# BMS_Enerdel_Adapter_rev5.net
KiCad netlist of a schematic drawn in EAGLE
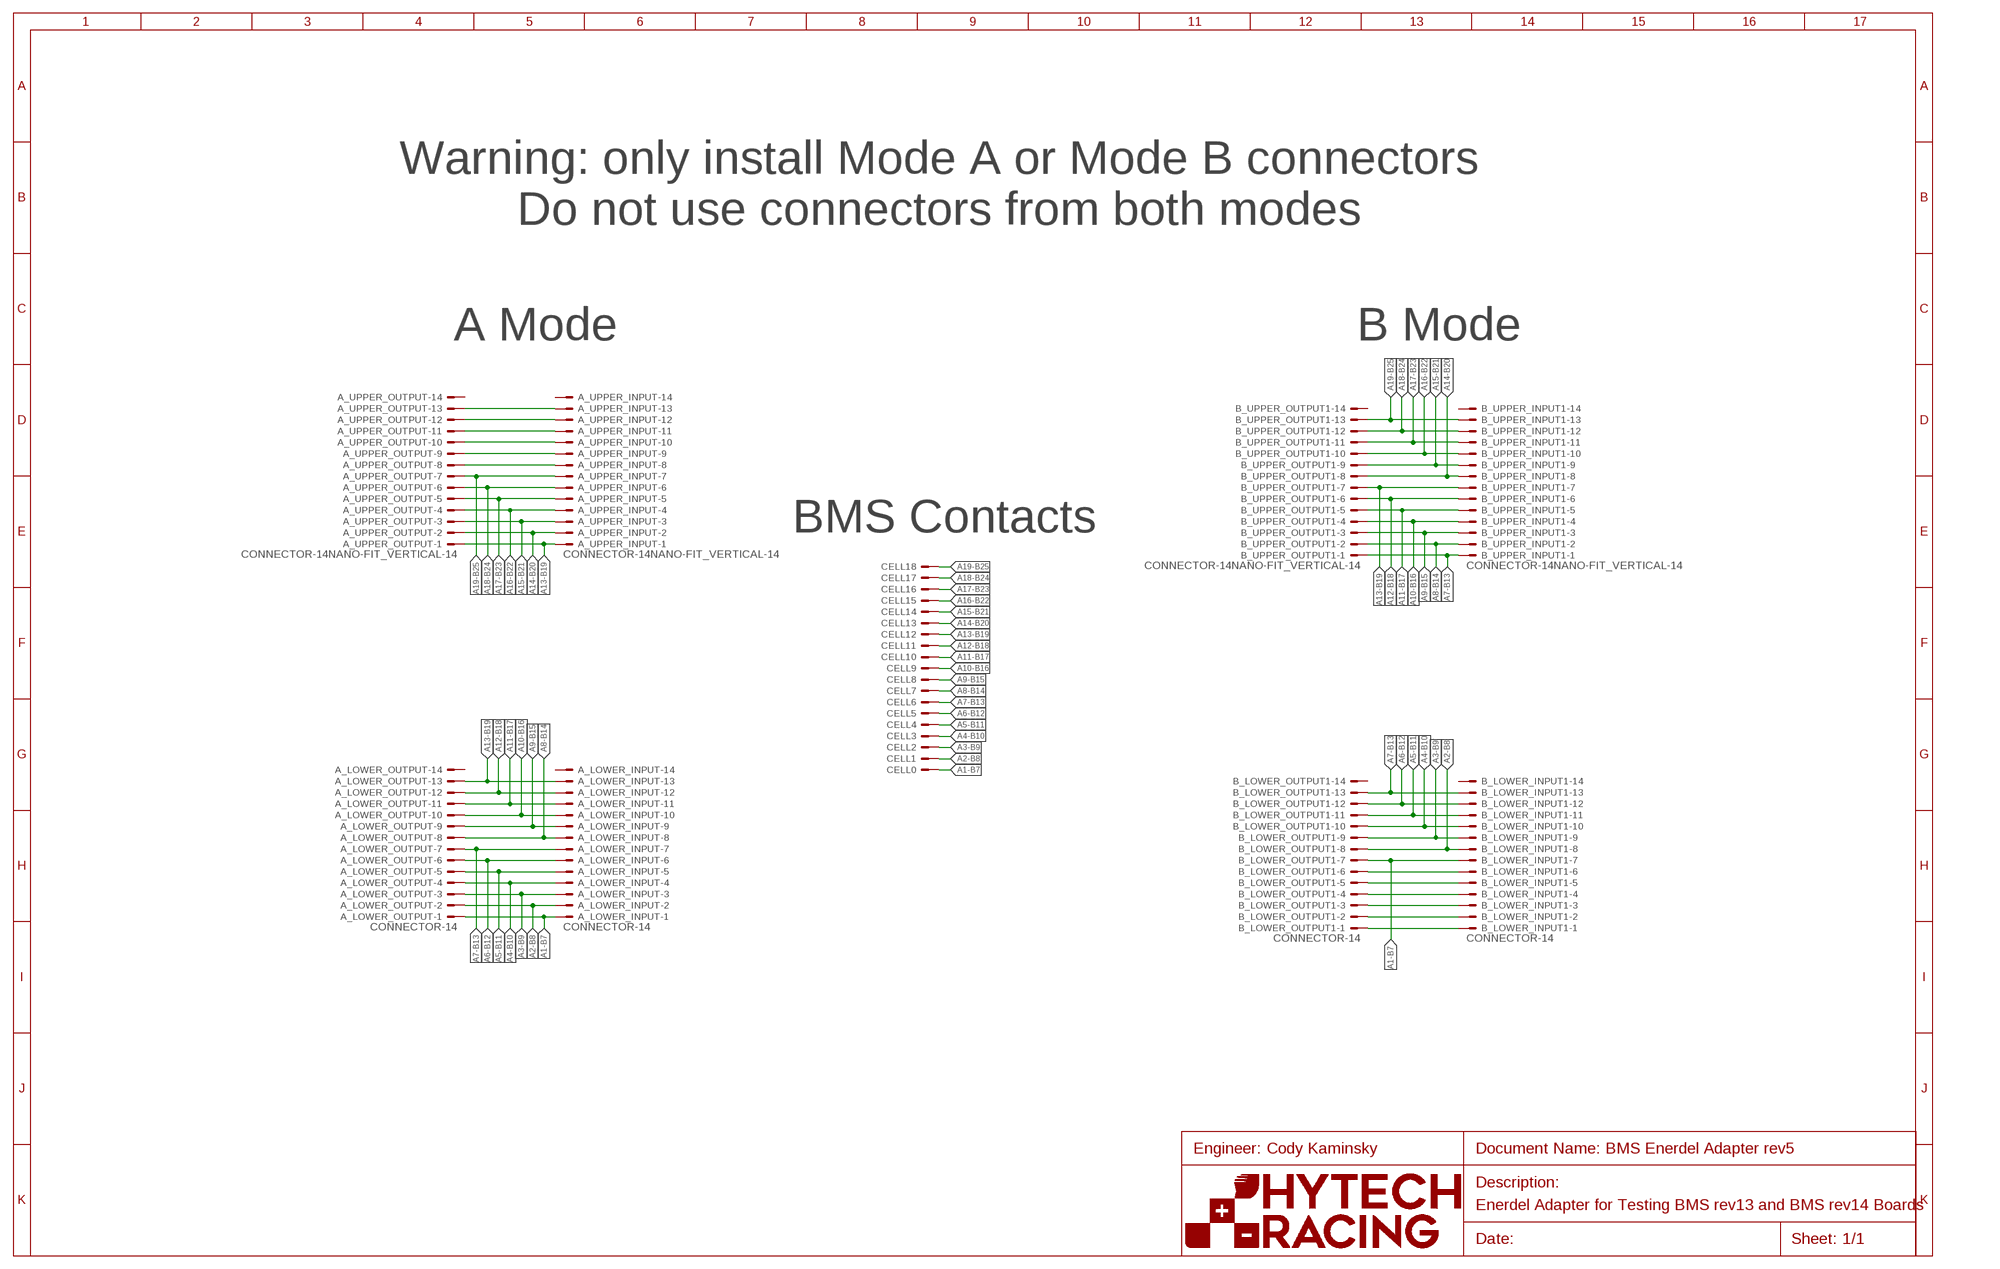
[diagram p0: schematic, sheet 1]

(export (version "E")
  (design (tool "Eeschema 10.0.6"))
  (components
    (comp (ref "A_LOWER_INPUT")
      (value "CONNECTOR-14")
      (footprint "eagle-import:MINIFIT_5566-14")
      (libsource (lib "eagle-import") (part "CONNECTOR-14"))
    )
    (comp (ref "A_LOWER_OUTPUT")
      (value "CONNECTOR-14")
      (footprint "eagle-import:MINIFIT_5566-14")
      (libsource (lib "eagle-import") (part "CONNECTOR-14"))
    )
    (comp (ref "A_UPPER_INPUT")
      (value "CONNECTOR-14NANO-FIT_VERTICAL-14")
      (footprint "eagle-import:NANO-FIT_VERTICAL-14")
      (libsource (lib "eagle-import") (part "CONNECTOR-14NANO-FIT_VERTICAL-14"))
    )
    (comp (ref "A_UPPER_OUTPUT")
      (value "CONNECTOR-14NANO-FIT_VERTICAL-14")
      (footprint "eagle-import:NANO-FIT_VERTICAL-14")
      (libsource (lib "eagle-import") (part "CONNECTOR-14NANO-FIT_VERTICAL-14"))
    )
    (comp (ref "B_LOWER_INPUT1")
      (value "CONNECTOR-14")
      (footprint "eagle-import:MINIFIT_5566-14")
      (libsource (lib "eagle-import") (part "CONNECTOR-14"))
    )
    (comp (ref "B_LOWER_OUTPUT1")
      (value "CONNECTOR-14")
      (footprint "eagle-import:MINIFIT_5566-14")
      (libsource (lib "eagle-import") (part "CONNECTOR-14"))
    )
    (comp (ref "B_UPPER_INPUT1")
      (value "CONNECTOR-14NANO-FIT_VERTICAL-14")
      (footprint "eagle-import:NANO-FIT_VERTICAL-14")
      (libsource (lib "eagle-import") (part "CONNECTOR-14NANO-FIT_VERTICAL-14"))
    )
    (comp (ref "B_UPPER_OUTPUT1")
      (value "CONNECTOR-14NANO-FIT_VERTICAL-14")
      (footprint "eagle-import:NANO-FIT_VERTICAL-14")
      (libsource (lib "eagle-import") (part "CONNECTOR-14NANO-FIT_VERTICAL-14"))
    )
    (comp (ref "CELL0")
      (value "BATTERY_SPRING_KEYSTONE5222")
      (footprint "eagle-import:KEYSTONE5222")
      (libsource (lib "eagle-import") (part "BATTERY_SPRING_KEYSTONE5222"))
    )
    (comp (ref "CELL1")
      (value "BATTERY_SPRING_KEYSTONE5222")
      (footprint "eagle-import:KEYSTONE5222")
      (libsource (lib "eagle-import") (part "BATTERY_SPRING_KEYSTONE5222"))
    )
    (comp (ref "CELL2")
      (value "BATTERY_SPRING_KEYSTONE5222")
      (footprint "eagle-import:KEYSTONE5222")
      (libsource (lib "eagle-import") (part "BATTERY_SPRING_KEYSTONE5222"))
    )
    (comp (ref "CELL3")
      (value "BATTERY_SPRING_KEYSTONE5222")
      (footprint "eagle-import:KEYSTONE5222")
      (libsource (lib "eagle-import") (part "BATTERY_SPRING_KEYSTONE5222"))
    )
    (comp (ref "CELL4")
      (value "BATTERY_SPRING_KEYSTONE5222")
      (footprint "eagle-import:KEYSTONE5222")
      (libsource (lib "eagle-import") (part "BATTERY_SPRING_KEYSTONE5222"))
    )
    (comp (ref "CELL5")
      (value "BATTERY_SPRING_KEYSTONE5222")
      (footprint "eagle-import:KEYSTONE5222")
      (libsource (lib "eagle-import") (part "BATTERY_SPRING_KEYSTONE5222"))
    )
    (comp (ref "CELL6")
      (value "BATTERY_SPRING_KEYSTONE5222")
      (footprint "eagle-import:KEYSTONE5222")
      (libsource (lib "eagle-import") (part "BATTERY_SPRING_KEYSTONE5222"))
    )
    (comp (ref "CELL7")
      (value "BATTERY_SPRING_KEYSTONE5222")
      (footprint "eagle-import:KEYSTONE5222")
      (libsource (lib "eagle-import") (part "BATTERY_SPRING_KEYSTONE5222"))
    )
    (comp (ref "CELL8")
      (value "BATTERY_SPRING_KEYSTONE5222")
      (footprint "eagle-import:KEYSTONE5222")
      (libsource (lib "eagle-import") (part "BATTERY_SPRING_KEYSTONE5222"))
    )
    (comp (ref "CELL9")
      (value "BATTERY_SPRING_KEYSTONE5222")
      (footprint "eagle-import:KEYSTONE5222")
      (libsource (lib "eagle-import") (part "BATTERY_SPRING_KEYSTONE5222"))
    )
    (comp (ref "CELL10")
      (value "BATTERY_SPRING_KEYSTONE5222")
      (footprint "eagle-import:KEYSTONE5222")
      (libsource (lib "eagle-import") (part "BATTERY_SPRING_KEYSTONE5222"))
    )
    (comp (ref "CELL11")
      (value "BATTERY_SPRING_KEYSTONE5222")
      (footprint "eagle-import:KEYSTONE5222")
      (libsource (lib "eagle-import") (part "BATTERY_SPRING_KEYSTONE5222"))
    )
    (comp (ref "CELL12")
      (value "BATTERY_SPRING_KEYSTONE5222")
      (footprint "eagle-import:KEYSTONE5222")
      (libsource (lib "eagle-import") (part "BATTERY_SPRING_KEYSTONE5222"))
    )
    (comp (ref "CELL13")
      (value "BATTERY_SPRING_KEYSTONE5222")
      (footprint "eagle-import:KEYSTONE5222")
      (libsource (lib "eagle-import") (part "BATTERY_SPRING_KEYSTONE5222"))
    )
    (comp (ref "CELL14")
      (value "BATTERY_SPRING_KEYSTONE5222")
      (footprint "eagle-import:KEYSTONE5222")
      (libsource (lib "eagle-import") (part "BATTERY_SPRING_KEYSTONE5222"))
    )
    (comp (ref "CELL15")
      (value "BATTERY_SPRING_KEYSTONE5222")
      (footprint "eagle-import:KEYSTONE5222")
      (libsource (lib "eagle-import") (part "BATTERY_SPRING_KEYSTONE5222"))
    )
    (comp (ref "CELL16")
      (value "BATTERY_SPRING_KEYSTONE5222")
      (footprint "eagle-import:KEYSTONE5222")
      (libsource (lib "eagle-import") (part "BATTERY_SPRING_KEYSTONE5222"))
    )
    (comp (ref "CELL17")
      (value "BATTERY_SPRING_KEYSTONE5222")
      (footprint "eagle-import:KEYSTONE5222")
      (libsource (lib "eagle-import") (part "BATTERY_SPRING_KEYSTONE5222"))
    )
    (comp (ref "CELL18")
      (value "BATTERY_SPRING_KEYSTONE5222")
      (footprint "eagle-import:KEYSTONE5222")
      (libsource (lib "eagle-import") (part "BATTERY_SPRING_KEYSTONE5222"))
    )
  )
  (nets
    (net (code "1") (name "A1-B7") (class "Default")
      (node (ref "A_LOWER_INPUT") (pin "1") (pinfunction "S_1") (pintype "passive"))
      (node (ref "A_LOWER_OUTPUT") (pin "1") (pinfunction "S_1") (pintype "passive"))
      (node (ref "B_LOWER_INPUT1") (pin "7") (pinfunction "S_7") (pintype "passive"))
      (node (ref "B_LOWER_OUTPUT1") (pin "7") (pinfunction "S_7") (pintype "passive"))
      (node (ref "CELL0") (pin "P$1") (pinfunction "S_P$1") (pintype "passive"))
    )
    (net (code "2") (name "A2-B8") (class "Default")
      (node (ref "A_LOWER_INPUT") (pin "2") (pinfunction "S_2") (pintype "passive"))
      (node (ref "A_LOWER_OUTPUT") (pin "2") (pinfunction "S_2") (pintype "passive"))
      (node (ref "B_LOWER_INPUT1") (pin "8") (pinfunction "S_8") (pintype "passive"))
      (node (ref "B_LOWER_OUTPUT1") (pin "8") (pinfunction "S_8") (pintype "passive"))
      (node (ref "CELL1") (pin "P$1") (pinfunction "S_P$1") (pintype "passive"))
    )
    (net (code "3") (name "A3-B9") (class "Default")
      (node (ref "A_LOWER_INPUT") (pin "3") (pinfunction "S_3") (pintype "passive"))
      (node (ref "A_LOWER_OUTPUT") (pin "3") (pinfunction "S_3") (pintype "passive"))
      (node (ref "B_LOWER_INPUT1") (pin "9") (pinfunction "S_9") (pintype "passive"))
      (node (ref "B_LOWER_OUTPUT1") (pin "9") (pinfunction "S_9") (pintype "passive"))
      (node (ref "CELL2") (pin "P$1") (pinfunction "S_P$1") (pintype "passive"))
    )
    (net (code "4") (name "A4-B10") (class "Default")
      (node (ref "A_LOWER_INPUT") (pin "4") (pinfunction "S_4") (pintype "passive"))
      (node (ref "A_LOWER_OUTPUT") (pin "4") (pinfunction "S_4") (pintype "passive"))
      (node (ref "B_LOWER_INPUT1") (pin "10") (pinfunction "S_10") (pintype "passive"))
      (node (ref "B_LOWER_OUTPUT1") (pin "10") (pinfunction "S_10") (pintype "passive"))
      (node (ref "CELL3") (pin "P$1") (pinfunction "S_P$1") (pintype "passive"))
    )
    (net (code "5") (name "A5-B11") (class "Default")
      (node (ref "A_LOWER_INPUT") (pin "5") (pinfunction "S_5") (pintype "passive"))
      (node (ref "A_LOWER_OUTPUT") (pin "5") (pinfunction "S_5") (pintype "passive"))
      (node (ref "B_LOWER_INPUT1") (pin "11") (pinfunction "S_11") (pintype "passive"))
      (node (ref "B_LOWER_OUTPUT1") (pin "11") (pinfunction "S_11") (pintype "passive"))
      (node (ref "CELL4") (pin "P$1") (pinfunction "S_P$1") (pintype "passive"))
    )
    (net (code "6") (name "A6-B12") (class "Default")
      (node (ref "A_LOWER_INPUT") (pin "6") (pinfunction "S_6") (pintype "passive"))
      (node (ref "A_LOWER_OUTPUT") (pin "6") (pinfunction "S_6") (pintype "passive"))
      (node (ref "B_LOWER_INPUT1") (pin "12") (pinfunction "S_12") (pintype "passive"))
      (node (ref "B_LOWER_OUTPUT1") (pin "12") (pinfunction "S_12") (pintype "passive"))
      (node (ref "CELL5") (pin "P$1") (pinfunction "S_P$1") (pintype "passive"))
    )
    (net (code "7") (name "A7-B13") (class "Default")
      (node (ref "A_LOWER_INPUT") (pin "7") (pinfunction "S_7") (pintype "passive"))
      (node (ref "A_LOWER_OUTPUT") (pin "7") (pinfunction "S_7") (pintype "passive"))
      (node (ref "B_LOWER_INPUT1") (pin "13") (pinfunction "S_13") (pintype "passive"))
      (node (ref "B_LOWER_OUTPUT1") (pin "13") (pinfunction "S_13") (pintype "passive"))
      (node (ref "B_UPPER_INPUT1") (pin "P$1") (pinfunction "S_P$1") (pintype "passive"))
      (node (ref "B_UPPER_OUTPUT1") (pin "P$1") (pinfunction "S_P$1") (pintype "passive"))
      (node (ref "CELL6") (pin "P$1") (pinfunction "S_P$1") (pintype "passive"))
    )
    (net (code "8") (name "A8-B14") (class "Default")
      (node (ref "A_LOWER_INPUT") (pin "8") (pinfunction "S_8") (pintype "passive"))
      (node (ref "A_LOWER_OUTPUT") (pin "8") (pinfunction "S_8") (pintype "passive"))
      (node (ref "B_UPPER_INPUT1") (pin "P$2") (pinfunction "S_P$2") (pintype "passive"))
      (node (ref "B_UPPER_OUTPUT1") (pin "P$2") (pinfunction "S_P$2") (pintype "passive"))
      (node (ref "CELL7") (pin "P$1") (pinfunction "S_P$1") (pintype "passive"))
    )
    (net (code "9") (name "A9-B15") (class "Default")
      (node (ref "A_LOWER_INPUT") (pin "9") (pinfunction "S_9") (pintype "passive"))
      (node (ref "A_LOWER_OUTPUT") (pin "9") (pinfunction "S_9") (pintype "passive"))
      (node (ref "B_UPPER_INPUT1") (pin "P$3") (pinfunction "S_P$3") (pintype "passive"))
      (node (ref "B_UPPER_OUTPUT1") (pin "P$3") (pinfunction "S_P$3") (pintype "passive"))
      (node (ref "CELL8") (pin "P$1") (pinfunction "S_P$1") (pintype "passive"))
    )
    (net (code "10") (name "A10-B16") (class "Default")
      (node (ref "A_LOWER_INPUT") (pin "10") (pinfunction "S_10") (pintype "passive"))
      (node (ref "A_LOWER_OUTPUT") (pin "10") (pinfunction "S_10") (pintype "passive"))
      (node (ref "B_UPPER_INPUT1") (pin "P$4") (pinfunction "S_P$4") (pintype "passive"))
      (node (ref "B_UPPER_OUTPUT1") (pin "P$4") (pinfunction "S_P$4") (pintype "passive"))
      (node (ref "CELL9") (pin "P$1") (pinfunction "S_P$1") (pintype "passive"))
    )
    (net (code "11") (name "A11-B17") (class "Default")
      (node (ref "A_LOWER_INPUT") (pin "11") (pinfunction "S_11") (pintype "passive"))
      (node (ref "A_LOWER_OUTPUT") (pin "11") (pinfunction "S_11") (pintype "passive"))
      (node (ref "B_UPPER_INPUT1") (pin "P$5") (pinfunction "S_P$5") (pintype "passive"))
      (node (ref "B_UPPER_OUTPUT1") (pin "P$5") (pinfunction "S_P$5") (pintype "passive"))
      (node (ref "CELL10") (pin "P$1") (pinfunction "S_P$1") (pintype "passive"))
    )
    (net (code "12") (name "A12-B18") (class "Default")
      (node (ref "A_LOWER_INPUT") (pin "12") (pinfunction "S_12") (pintype "passive"))
      (node (ref "A_LOWER_OUTPUT") (pin "12") (pinfunction "S_12") (pintype "passive"))
      (node (ref "B_UPPER_INPUT1") (pin "P$6") (pinfunction "S_P$6") (pintype "passive"))
      (node (ref "B_UPPER_OUTPUT1") (pin "P$6") (pinfunction "S_P$6") (pintype "passive"))
      (node (ref "CELL11") (pin "P$1") (pinfunction "S_P$1") (pintype "passive"))
    )
    (net (code "13") (name "A13-B19") (class "Default")
      (node (ref "A_LOWER_INPUT") (pin "13") (pinfunction "S_13") (pintype "passive"))
      (node (ref "A_LOWER_OUTPUT") (pin "13") (pinfunction "S_13") (pintype "passive"))
      (node (ref "A_UPPER_INPUT") (pin "P$1") (pinfunction "S_P$1") (pintype "passive"))
      (node (ref "A_UPPER_OUTPUT") (pin "P$1") (pinfunction "S_P$1") (pintype "passive"))
      (node (ref "B_UPPER_INPUT1") (pin "P$7") (pinfunction "S_P$7") (pintype "passive"))
      (node (ref "B_UPPER_OUTPUT1") (pin "P$7") (pinfunction "S_P$7") (pintype "passive"))
      (node (ref "CELL12") (pin "P$1") (pinfunction "S_P$1") (pintype "passive"))
    )
    (net (code "14") (name "A14-B20") (class "Default")
      (node (ref "A_UPPER_INPUT") (pin "P$2") (pinfunction "S_P$2") (pintype "passive"))
      (node (ref "A_UPPER_OUTPUT") (pin "P$2") (pinfunction "S_P$2") (pintype "passive"))
      (node (ref "B_UPPER_INPUT1") (pin "P$8") (pinfunction "S_P$8") (pintype "passive"))
      (node (ref "B_UPPER_OUTPUT1") (pin "P$8") (pinfunction "S_P$8") (pintype "passive"))
      (node (ref "CELL13") (pin "P$1") (pinfunction "S_P$1") (pintype "passive"))
    )
    (net (code "15") (name "A15-B21") (class "Default")
      (node (ref "A_UPPER_INPUT") (pin "P$3") (pinfunction "S_P$3") (pintype "passive"))
      (node (ref "A_UPPER_OUTPUT") (pin "P$3") (pinfunction "S_P$3") (pintype "passive"))
      (node (ref "B_UPPER_INPUT1") (pin "P$9") (pinfunction "S_P$9") (pintype "passive"))
      (node (ref "B_UPPER_OUTPUT1") (pin "P$9") (pinfunction "S_P$9") (pintype "passive"))
      (node (ref "CELL14") (pin "P$1") (pinfunction "S_P$1") (pintype "passive"))
    )
    (net (code "16") (name "A16-B22") (class "Default")
      (node (ref "A_UPPER_INPUT") (pin "P$4") (pinfunction "S_P$4") (pintype "passive"))
      (node (ref "A_UPPER_OUTPUT") (pin "P$4") (pinfunction "S_P$4") (pintype "passive"))
      (node (ref "B_UPPER_INPUT1") (pin "P$10") (pinfunction "S_P$10") (pintype "passive"))
      (node (ref "B_UPPER_OUTPUT1") (pin "P$10") (pinfunction "S_P$10") (pintype "passive"))
      (node (ref "CELL15") (pin "P$1") (pinfunction "S_P$1") (pintype "passive"))
    )
    (net (code "17") (name "A17-B23") (class "Default")
      (node (ref "A_UPPER_INPUT") (pin "P$5") (pinfunction "S_P$5") (pintype "passive"))
      (node (ref "A_UPPER_OUTPUT") (pin "P$5") (pinfunction "S_P$5") (pintype "passive"))
      (node (ref "B_UPPER_INPUT1") (pin "P$11") (pinfunction "S_P$11") (pintype "passive"))
      (node (ref "B_UPPER_OUTPUT1") (pin "P$11") (pinfunction "S_P$11") (pintype "passive"))
      (node (ref "CELL16") (pin "P$1") (pinfunction "S_P$1") (pintype "passive"))
    )
    (net (code "18") (name "A18-B24") (class "Default")
      (node (ref "A_UPPER_INPUT") (pin "P$6") (pinfunction "S_P$6") (pintype "passive"))
      (node (ref "A_UPPER_OUTPUT") (pin "P$6") (pinfunction "S_P$6") (pintype "passive"))
      (node (ref "B_UPPER_INPUT1") (pin "P$12") (pinfunction "S_P$12") (pintype "passive"))
      (node (ref "B_UPPER_OUTPUT1") (pin "P$12") (pinfunction "S_P$12") (pintype "passive"))
      (node (ref "CELL17") (pin "P$1") (pinfunction "S_P$1") (pintype "passive"))
    )
    (net (code "19") (name "A19-B25") (class "Default")
      (node (ref "A_UPPER_INPUT") (pin "P$7") (pinfunction "S_P$7") (pintype "passive"))
      (node (ref "A_UPPER_OUTPUT") (pin "P$7") (pinfunction "S_P$7") (pintype "passive"))
      (node (ref "B_UPPER_INPUT1") (pin "P$13") (pinfunction "S_P$13") (pintype "passive"))
      (node (ref "B_UPPER_OUTPUT1") (pin "P$13") (pinfunction "S_P$13") (pintype "passive"))
      (node (ref "CELL18") (pin "P$1") (pinfunction "S_P$1") (pintype "passive"))
    )
    (net (code "20") (name "Net-(A_UPPER_INPUTB-S)") (class "Default")
      (node (ref "A_UPPER_INPUT") (pin "P$10") (pinfunction "S_P$10") (pintype "passive"))
      (node (ref "A_UPPER_OUTPUT") (pin "P$10") (pinfunction "S_P$10") (pintype "passive"))
    )
    (net (code "21") (name "Net-(A_UPPER_INPUTC-S)") (class "Default")
      (node (ref "A_UPPER_INPUT") (pin "P$11") (pinfunction "S_P$11") (pintype "passive"))
      (node (ref "A_UPPER_OUTPUT") (pin "P$11") (pinfunction "S_P$11") (pintype "passive"))
    )
    (net (code "22") (name "Net-(A_UPPER_INPUTD-S)") (class "Default")
      (node (ref "A_UPPER_INPUT") (pin "P$12") (pinfunction "S_P$12") (pintype "passive"))
      (node (ref "A_UPPER_OUTPUT") (pin "P$12") (pinfunction "S_P$12") (pintype "passive"))
    )
    (net (code "23") (name "Net-(A_UPPER_INPUTE-S)") (class "Default")
      (node (ref "A_UPPER_INPUT") (pin "P$13") (pinfunction "S_P$13") (pintype "passive"))
      (node (ref "A_UPPER_OUTPUT") (pin "P$13") (pinfunction "S_P$13") (pintype "passive"))
    )
    (net (code "24") (name "Net-(A_UPPER_INPUTM-S)") (class "Default")
      (node (ref "A_UPPER_INPUT") (pin "P$8") (pinfunction "S_P$8") (pintype "passive"))
      (node (ref "A_UPPER_OUTPUT") (pin "P$8") (pinfunction "S_P$8") (pintype "passive"))
    )
    (net (code "25") (name "Net-(A_UPPER_INPUTN-S)") (class "Default")
      (node (ref "A_UPPER_INPUT") (pin "P$9") (pinfunction "S_P$9") (pintype "passive"))
      (node (ref "A_UPPER_OUTPUT") (pin "P$9") (pinfunction "S_P$9") (pintype "passive"))
    )
    (net (code "26") (name "Net-(B_LOWER_INPUT1A-S)") (class "Default")
      (node (ref "B_LOWER_INPUT1") (pin "1") (pinfunction "S_1") (pintype "passive"))
      (node (ref "B_LOWER_OUTPUT1") (pin "1") (pinfunction "S_1") (pintype "passive"))
    )
    (net (code "27") (name "Net-(B_LOWER_INPUT1G-S)") (class "Default")
      (node (ref "B_LOWER_INPUT1") (pin "2") (pinfunction "S_2") (pintype "passive"))
      (node (ref "B_LOWER_OUTPUT1") (pin "2") (pinfunction "S_2") (pintype "passive"))
    )
    (net (code "28") (name "Net-(B_LOWER_INPUT1H-S)") (class "Default")
      (node (ref "B_LOWER_INPUT1") (pin "3") (pinfunction "S_3") (pintype "passive"))
      (node (ref "B_LOWER_OUTPUT1") (pin "3") (pinfunction "S_3") (pintype "passive"))
    )
    (net (code "29") (name "Net-(B_LOWER_INPUT1I-S)") (class "Default")
      (node (ref "B_LOWER_INPUT1") (pin "4") (pinfunction "S_4") (pintype "passive"))
      (node (ref "B_LOWER_OUTPUT1") (pin "4") (pinfunction "S_4") (pintype "passive"))
    )
    (net (code "30") (name "Net-(B_LOWER_INPUT1J-S)") (class "Default")
      (node (ref "B_LOWER_INPUT1") (pin "5") (pinfunction "S_5") (pintype "passive"))
      (node (ref "B_LOWER_OUTPUT1") (pin "5") (pinfunction "S_5") (pintype "passive"))
    )
    (net (code "31") (name "Net-(B_LOWER_INPUT1K-S)") (class "Default")
      (node (ref "B_LOWER_INPUT1") (pin "6") (pinfunction "S_6") (pintype "passive"))
      (node (ref "B_LOWER_OUTPUT1") (pin "6") (pinfunction "S_6") (pintype "passive"))
    )
    (net (code "32") (name "unconnected-(A_LOWER_INPUTF-S-Pad14)") (class "Default")
      (node (ref "A_LOWER_INPUT") (pin "14") (pinfunction "S_14") (pintype "passive"))
    )
    (net (code "33") (name "unconnected-(A_LOWER_OUTPUTF-S-Pad14)") (class "Default")
      (node (ref "A_LOWER_OUTPUT") (pin "14") (pinfunction "S_14") (pintype "passive"))
    )
    (net (code "34") (name "unconnected-(A_UPPER_INPUTF-S-PadP$14)") (class "Default")
      (node (ref "A_UPPER_INPUT") (pin "P$14") (pinfunction "S_P$14") (pintype "passive"))
    )
    (net (code "35") (name "unconnected-(A_UPPER_OUTPUTF-S-PadP$14)") (class "Default")
      (node (ref "A_UPPER_OUTPUT") (pin "P$14") (pinfunction "S_P$14") (pintype "passive"))
    )
    (net (code "36") (name "unconnected-(B_LOWER_INPUT1F-S-Pad14)") (class "Default")
      (node (ref "B_LOWER_INPUT1") (pin "14") (pinfunction "S_14") (pintype "passive"))
    )
    (net (code "37") (name "unconnected-(B_LOWER_OUTPUT1F-S-Pad14)") (class "Default")
      (node (ref "B_LOWER_OUTPUT1") (pin "14") (pinfunction "S_14") (pintype "passive"))
    )
    (net (code "38") (name "unconnected-(B_UPPER_INPUT1F-S-PadP$14)") (class "Default")
      (node (ref "B_UPPER_INPUT1") (pin "P$14") (pinfunction "S_P$14") (pintype "passive"))
    )
    (net (code "39") (name "unconnected-(B_UPPER_OUTPUT1F-S-PadP$14)") (class "Default")
      (node (ref "B_UPPER_OUTPUT1") (pin "P$14") (pinfunction "S_P$14") (pintype "passive"))
    )
  )
)
